# Device.net
KiCad netlist of a schematic drawn in Altium Designer
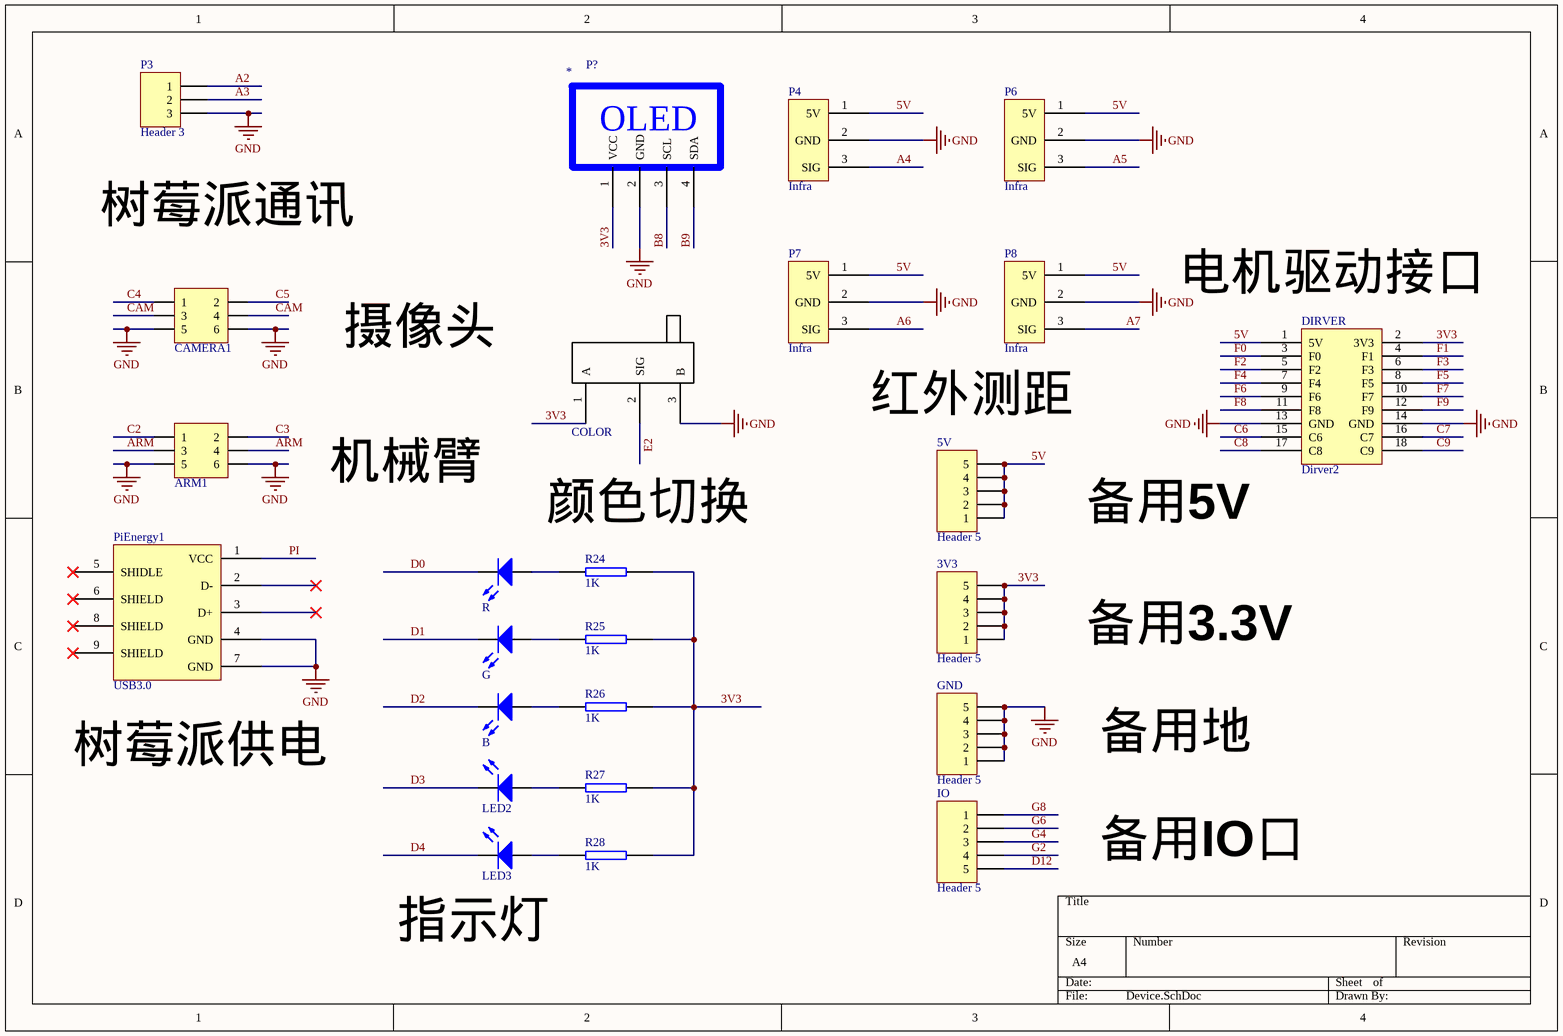
[diagram p0: Device.SchDoc]

(export (version "E")
  (design (tool "Eeschema 10.0.6"))
  (components
    (comp (ref "*") (value "P?") (footprint "OLED") (libsource (lib "robot2") (part "OLED")))
    (comp (ref "3V3")
      (value "Header 5")
      (footprint "HDR1X5")
      (description "Header, 5-Pin")
      (fields (field (name "PUBLISHER") "Altium Limited"))
      (libsource (lib "Miscellaneous Connectors") (part "Header 5"))
    )
    (comp (ref "5V")
      (value "Header 5")
      (footprint "HDR1X5")
      (description "Header, 5-Pin")
      (fields (field (name "PUBLISHER") "Altium Limited"))
      (libsource (lib "Miscellaneous Connectors") (part "Header 5"))
    )
    (comp (ref "ARM1")
      (value "Header3X2")
      (footprint "HDR-3X2")
      (description "3*2P接插件")
      (fields (field (name "版权归属") "源创客"))
      (libsource (lib "PCB_Project2") (part "Header 3X2"))
    )
    (comp (ref "B") (value "LED0") (footprint "LED[0805]") (libsource (lib "Robot") (part "LED0")))
    (comp (ref "CAMERA1")
      (value "Header3X2")
      (footprint "HDR-3X2")
      (description "3*2P接插件")
      (fields (field (name "版权归属") "源创客"))
      (libsource (lib "PCB_Project2") (part "Header 3X2"))
    )
    (comp (ref "COLOR") (value "COLOR") (footprint "KEY") (libsource (lib "robot2") (part "key")))
    (comp (ref "DIRVER") (value "Dirver2") (footprint "DIRVER2") (libsource (lib "robot2") (part "Dirver2")))
    (comp (ref "G") (value "LED0") (footprint "LED[0805]") (libsource (lib "Robot") (part "LED0")))
    (comp (ref "GND")
      (value "Header 5")
      (footprint "HDR1X5")
      (description "Header, 5-Pin")
      (fields (field (name "PUBLISHER") "Altium Limited"))
      (libsource (lib "Miscellaneous Connectors") (part "Header 5"))
    )
    (comp (ref "IO")
      (value "Header 5")
      (footprint "HDR1X5")
      (description "Header, 5-Pin")
      (fields (field (name "PUBLISHER") "Altium Limited"))
      (libsource (lib "") (part "Header 5_1"))
    )
    (comp (ref "LED2") (value "LED0") (footprint "LED[0805]") (libsource (lib "Robot") (part "LED0")))
    (comp (ref "LED3") (value "LED0") (footprint "LED[0805]") (libsource (lib "Robot") (part "LED0")))
    (comp (ref "P3")
      (value "Header 3")
      (footprint "HDR1X3")
      (description "Header, 3-Pin")
      (fields (field (name "PUBLISHER") "Altium Limited"))
      (libsource (lib "Miscellaneous Connectors") (part "Header 3"))
    )
    (comp (ref "P4") (value "Infra") (footprint "Infra") (libsource (lib "Robot") (part "Infra")))
    (comp (ref "P6") (value "Infra") (footprint "Infra") (libsource (lib "Robot") (part "Infra")))
    (comp (ref "P7") (value "Infra") (footprint "Infra") (libsource (lib "Robot") (part "Infra")))
    (comp (ref "P8") (value "Infra") (footprint "Infra") (libsource (lib "Robot") (part "Infra")))
    (comp (ref "PiEnergy1") (value "USB3.0") (footprint "USB3.0") (libsource (lib "Robot") (part "USB3.0")))
    (comp (ref "R") (value "LED0") (footprint "LED[0805]") (libsource (lib "Robot") (part "LED0")))
    (comp (ref "R24") (value "1K") (footprint "R0805") (libsource (lib "Robot") (part "RES")))
    (comp (ref "R25") (value "1K") (footprint "R0805") (libsource (lib "Robot") (part "RES")))
    (comp (ref "R26") (value "1K") (footprint "R0805") (libsource (lib "Robot") (part "RES")))
    (comp (ref "R27") (value "1K") (footprint "R0805") (libsource (lib "Robot") (part "RES")))
    (comp (ref "R28") (value "1K") (footprint "R0805") (libsource (lib "Robot") (part "RES")))
  )
  (nets
    (net (code "1") (name "/3V3") (class "Default")
      (node (ref "*") (pin "1") (pinfunction "VCC_1") (pintype "passive"))
      (node (ref "3V3") (pin "1") (pinfunction "1_1") (pintype "passive"))
      (node (ref "3V3") (pin "2") (pinfunction "2_2") (pintype "passive"))
      (node (ref "3V3") (pin "3") (pinfunction "3_3") (pintype "passive"))
      (node (ref "3V3") (pin "4") (pinfunction "4_4") (pintype "passive"))
      (node (ref "3V3") (pin "5") (pinfunction "5_5") (pintype "passive"))
      (node (ref "COLOR") (pin "1") (pinfunction "A_1") (pintype "passive"))
      (node (ref "DIRVER") (pin "2") (pinfunction "3V3_2") (pintype "passive"))
      (node (ref "R24") (pin "2") (pinfunction "2_2") (pintype "passive"))
      (node (ref "R25") (pin "2") (pinfunction "2_2") (pintype "passive"))
      (node (ref "R26") (pin "2") (pinfunction "2_2") (pintype "passive"))
      (node (ref "R27") (pin "1") (pinfunction "1_1") (pintype "passive"))
      (node (ref "R28") (pin "1") (pinfunction "1_1") (pintype "passive"))
    )
    (net (code "2") (name "/5V") (class "Default")
      (node (ref "5V") (pin "1") (pinfunction "1_1") (pintype "passive"))
      (node (ref "5V") (pin "2") (pinfunction "2_2") (pintype "passive"))
      (node (ref "5V") (pin "3") (pinfunction "3_3") (pintype "passive"))
      (node (ref "5V") (pin "4") (pinfunction "4_4") (pintype "passive"))
      (node (ref "5V") (pin "5") (pinfunction "5_5") (pintype "passive"))
      (node (ref "DIRVER") (pin "1") (pinfunction "5V_1") (pintype "passive"))
      (node (ref "P4") (pin "1") (pinfunction "5V_1") (pintype "passive"))
      (node (ref "P6") (pin "1") (pinfunction "5V_1") (pintype "passive"))
      (node (ref "P7") (pin "1") (pinfunction "5V_1") (pintype "passive"))
      (node (ref "P8") (pin "1") (pinfunction "5V_1") (pintype "passive"))
    )
    (net (code "3") (name "/A2") (class "Default")
      (node (ref "P3") (pin "1") (pinfunction "1_1") (pintype "passive"))
    )
    (net (code "4") (name "/A3") (class "Default")
      (node (ref "P3") (pin "2") (pinfunction "2_2") (pintype "passive"))
    )
    (net (code "5") (name "/A4") (class "Default")
      (node (ref "P4") (pin "3") (pinfunction "SIG_3") (pintype "passive"))
    )
    (net (code "6") (name "/A5") (class "Default")
      (node (ref "P6") (pin "3") (pinfunction "SIG_3") (pintype "passive"))
    )
    (net (code "7") (name "/A6") (class "Default")
      (node (ref "P7") (pin "3") (pinfunction "SIG_3") (pintype "passive"))
    )
    (net (code "8") (name "/A7") (class "Default")
      (node (ref "P8") (pin "3") (pinfunction "SIG_3") (pintype "passive"))
    )
    (net (code "9") (name "/ARM") (class "Default")
      (node (ref "ARM1") (pin "3") (pinfunction "3_3") (pintype "passive"))
      (node (ref "ARM1") (pin "4") (pinfunction "4_4") (pintype "passive"))
    )
    (net (code "10") (name "/B8") (class "Default")
      (node (ref "*") (pin "3") (pinfunction "SCL_3") (pintype "passive"))
    )
    (net (code "11") (name "/B9") (class "Default")
      (node (ref "*") (pin "4") (pinfunction "SDA_4") (pintype "passive"))
    )
    (net (code "12") (name "/C2") (class "Default")
      (node (ref "ARM1") (pin "1") (pinfunction "1_1") (pintype "passive"))
    )
    (net (code "13") (name "/C3") (class "Default")
      (node (ref "ARM1") (pin "2") (pinfunction "2_2") (pintype "passive"))
    )
    (net (code "14") (name "/C4") (class "Default")
      (node (ref "CAMERA1") (pin "1") (pinfunction "1_1") (pintype "passive"))
    )
    (net (code "15") (name "/C5") (class "Default")
      (node (ref "CAMERA1") (pin "2") (pinfunction "2_2") (pintype "passive"))
    )
    (net (code "16") (name "/C6") (class "Default")
      (node (ref "DIRVER") (pin "15") (pinfunction "C6_15") (pintype "passive"))
    )
    (net (code "17") (name "/C7") (class "Default")
      (node (ref "DIRVER") (pin "16") (pinfunction "C7_16") (pintype "passive"))
    )
    (net (code "18") (name "/C8") (class "Default")
      (node (ref "DIRVER") (pin "17") (pinfunction "C8_17") (pintype "passive"))
    )
    (net (code "19") (name "/C9") (class "Default")
      (node (ref "DIRVER") (pin "18") (pinfunction "C9_18") (pintype "passive"))
    )
    (net (code "20") (name "/CAM") (class "Default")
      (node (ref "CAMERA1") (pin "3") (pinfunction "3_3") (pintype "passive"))
      (node (ref "CAMERA1") (pin "4") (pinfunction "4_4") (pintype "passive"))
    )
    (net (code "21") (name "/D0") (class "Default")
      (node (ref "R") (pin "2") (pinfunction "K_2") (pintype "passive"))
    )
    (net (code "22") (name "/D1") (class "Default")
      (node (ref "G") (pin "2") (pinfunction "K_2") (pintype "passive"))
    )
    (net (code "23") (name "/D2") (class "Default")
      (node (ref "B") (pin "2") (pinfunction "K_2") (pintype "passive"))
    )
    (net (code "24") (name "/D3") (class "Default")
      (node (ref "LED2") (pin "2") (pinfunction "K_2") (pintype "passive"))
    )
    (net (code "25") (name "/D4") (class "Default")
      (node (ref "LED3") (pin "2") (pinfunction "K_2") (pintype "passive"))
    )
    (net (code "26") (name "/D12") (class "Default")
      (node (ref "IO") (pin "5") (pinfunction "5_5") (pintype "passive"))
    )
    (net (code "27") (name "/E2") (class "Default")
      (node (ref "COLOR") (pin "2") (pinfunction "SIG_2") (pintype "passive"))
    )
    (net (code "28") (name "/F0") (class "Default")
      (node (ref "DIRVER") (pin "3") (pinfunction "F0_3") (pintype "passive"))
    )
    (net (code "29") (name "/F1") (class "Default")
      (node (ref "DIRVER") (pin "4") (pinfunction "F1_4") (pintype "passive"))
    )
    (net (code "30") (name "/F2") (class "Default")
      (node (ref "DIRVER") (pin "5") (pinfunction "F2_5") (pintype "passive"))
    )
    (net (code "31") (name "/F3") (class "Default")
      (node (ref "DIRVER") (pin "6") (pinfunction "F3_6") (pintype "passive"))
    )
    (net (code "32") (name "/F4") (class "Default")
      (node (ref "DIRVER") (pin "7") (pinfunction "F4_7") (pintype "passive"))
    )
    (net (code "33") (name "/F5") (class "Default")
      (node (ref "DIRVER") (pin "8") (pinfunction "F5_8") (pintype "passive"))
    )
    (net (code "34") (name "/F6") (class "Default")
      (node (ref "DIRVER") (pin "9") (pinfunction "F6_9") (pintype "passive"))
    )
    (net (code "35") (name "/F7") (class "Default")
      (node (ref "DIRVER") (pin "10") (pinfunction "F7_10") (pintype "passive"))
    )
    (net (code "36") (name "/F8") (class "Default")
      (node (ref "DIRVER") (pin "11") (pinfunction "F8_11") (pintype "passive"))
    )
    (net (code "37") (name "/F9") (class "Default")
      (node (ref "DIRVER") (pin "12") (pinfunction "F9_12") (pintype "passive"))
    )
    (net (code "38") (name "/G2") (class "Default")
      (node (ref "IO") (pin "4") (pinfunction "4_4") (pintype "passive"))
    )
    (net (code "39") (name "/G4") (class "Default")
      (node (ref "IO") (pin "3") (pinfunction "3_3") (pintype "passive"))
    )
    (net (code "40") (name "/G6") (class "Default")
      (node (ref "IO") (pin "2") (pinfunction "2_2") (pintype "passive"))
    )
    (net (code "41") (name "/G8") (class "Default")
      (node (ref "IO") (pin "1") (pinfunction "1_1") (pintype "passive"))
    )
    (net (code "42") (name "/PI") (class "Default")
      (node (ref "PiEnergy1") (pin "1") (pinfunction "VCC_1") (pintype "passive"))
    )
    (net (code "43") (name "GND") (class "Default")
      (node (ref "*") (pin "2") (pinfunction "GND_2") (pintype "passive"))
      (node (ref "ARM1") (pin "5") (pinfunction "5_5") (pintype "passive"))
      (node (ref "ARM1") (pin "6") (pinfunction "6_6") (pintype "passive"))
      (node (ref "CAMERA1") (pin "5") (pinfunction "5_5") (pintype "passive"))
      (node (ref "CAMERA1") (pin "6") (pinfunction "6_6") (pintype "passive"))
      (node (ref "COLOR") (pin "3") (pinfunction "B_3") (pintype "passive"))
      (node (ref "DIRVER") (pin "13") (pinfunction "GND_13") (pintype "passive"))
      (node (ref "DIRVER") (pin "14") (pinfunction "GND_14") (pintype "passive"))
      (node (ref "GND") (pin "1") (pinfunction "1_1") (pintype "passive"))
      (node (ref "GND") (pin "2") (pinfunction "2_2") (pintype "passive"))
      (node (ref "GND") (pin "3") (pinfunction "3_3") (pintype "passive"))
      (node (ref "GND") (pin "4") (pinfunction "4_4") (pintype "passive"))
      (node (ref "GND") (pin "5") (pinfunction "5_5") (pintype "passive"))
      (node (ref "P3") (pin "3") (pinfunction "3_3") (pintype "passive"))
      (node (ref "P4") (pin "2") (pinfunction "GND_2") (pintype "passive"))
      (node (ref "P6") (pin "2") (pinfunction "GND_2") (pintype "passive"))
      (node (ref "P7") (pin "2") (pinfunction "GND_2") (pintype "passive"))
      (node (ref "P8") (pin "2") (pinfunction "GND_2") (pintype "passive"))
      (node (ref "PiEnergy1") (pin "4") (pinfunction "GND_4") (pintype "passive"))
      (node (ref "PiEnergy1") (pin "7") (pinfunction "GND_7") (pintype "passive"))
    )
    (net (code "44") (name "Net-(B-A)") (class "Default")
      (node (ref "B") (pin "1") (pinfunction "A_1") (pintype "passive"))
      (node (ref "R26") (pin "1") (pinfunction "1_1") (pintype "passive"))
    )
    (net (code "45") (name "Net-(G-A)") (class "Default")
      (node (ref "G") (pin "1") (pinfunction "A_1") (pintype "passive"))
      (node (ref "R25") (pin "1") (pinfunction "1_1") (pintype "passive"))
    )
    (net (code "46") (name "Net-(LED2-A)") (class "Default")
      (node (ref "LED2") (pin "1") (pinfunction "A_1") (pintype "passive"))
      (node (ref "R27") (pin "2") (pinfunction "2_2") (pintype "passive"))
    )
    (net (code "47") (name "Net-(LED3-A)") (class "Default")
      (node (ref "LED3") (pin "1") (pinfunction "A_1") (pintype "passive"))
      (node (ref "R28") (pin "2") (pinfunction "2_2") (pintype "passive"))
    )
    (net (code "48") (name "Net-(R-A)") (class "Default")
      (node (ref "R") (pin "1") (pinfunction "A_1") (pintype "passive"))
      (node (ref "R24") (pin "1") (pinfunction "1_1") (pintype "passive"))
    )
    (net (code "49") (name "unconnected-(PiEnergy1-D+-Pad3)") (class "Default")
      (node (ref "PiEnergy1") (pin "3") (pinfunction "D+_3") (pintype "passive+no_connect"))
    )
    (net (code "50") (name "unconnected-(PiEnergy1-D--Pad2)") (class "Default")
      (node (ref "PiEnergy1") (pin "2") (pinfunction "D-_2") (pintype "passive+no_connect"))
    )
    (net (code "51") (name "unconnected-(PiEnergy1-SHIDLE-Pad5)") (class "Default")
      (node (ref "PiEnergy1") (pin "5") (pinfunction "SHIDLE_5") (pintype "passive+no_connect"))
    )
    (net (code "52") (name "unconnected-(PiEnergy1-SHIELD-Pad6)") (class "Default")
      (node (ref "PiEnergy1") (pin "6") (pinfunction "SHIELD_6") (pintype "passive+no_connect"))
    )
    (net (code "53") (name "unconnected-(PiEnergy1-SHIELD-Pad8)") (class "Default")
      (node (ref "PiEnergy1") (pin "8") (pinfunction "SHIELD_8") (pintype "passive+no_connect"))
    )
    (net (code "54") (name "unconnected-(PiEnergy1-SHIELD-Pad9)") (class "Default")
      (node (ref "PiEnergy1") (pin "9") (pinfunction "SHIELD_9") (pintype "passive+no_connect"))
    )
  )
)
